# Discovery_Board.net
KiCad netlist of a schematic drawn in Altium Designer
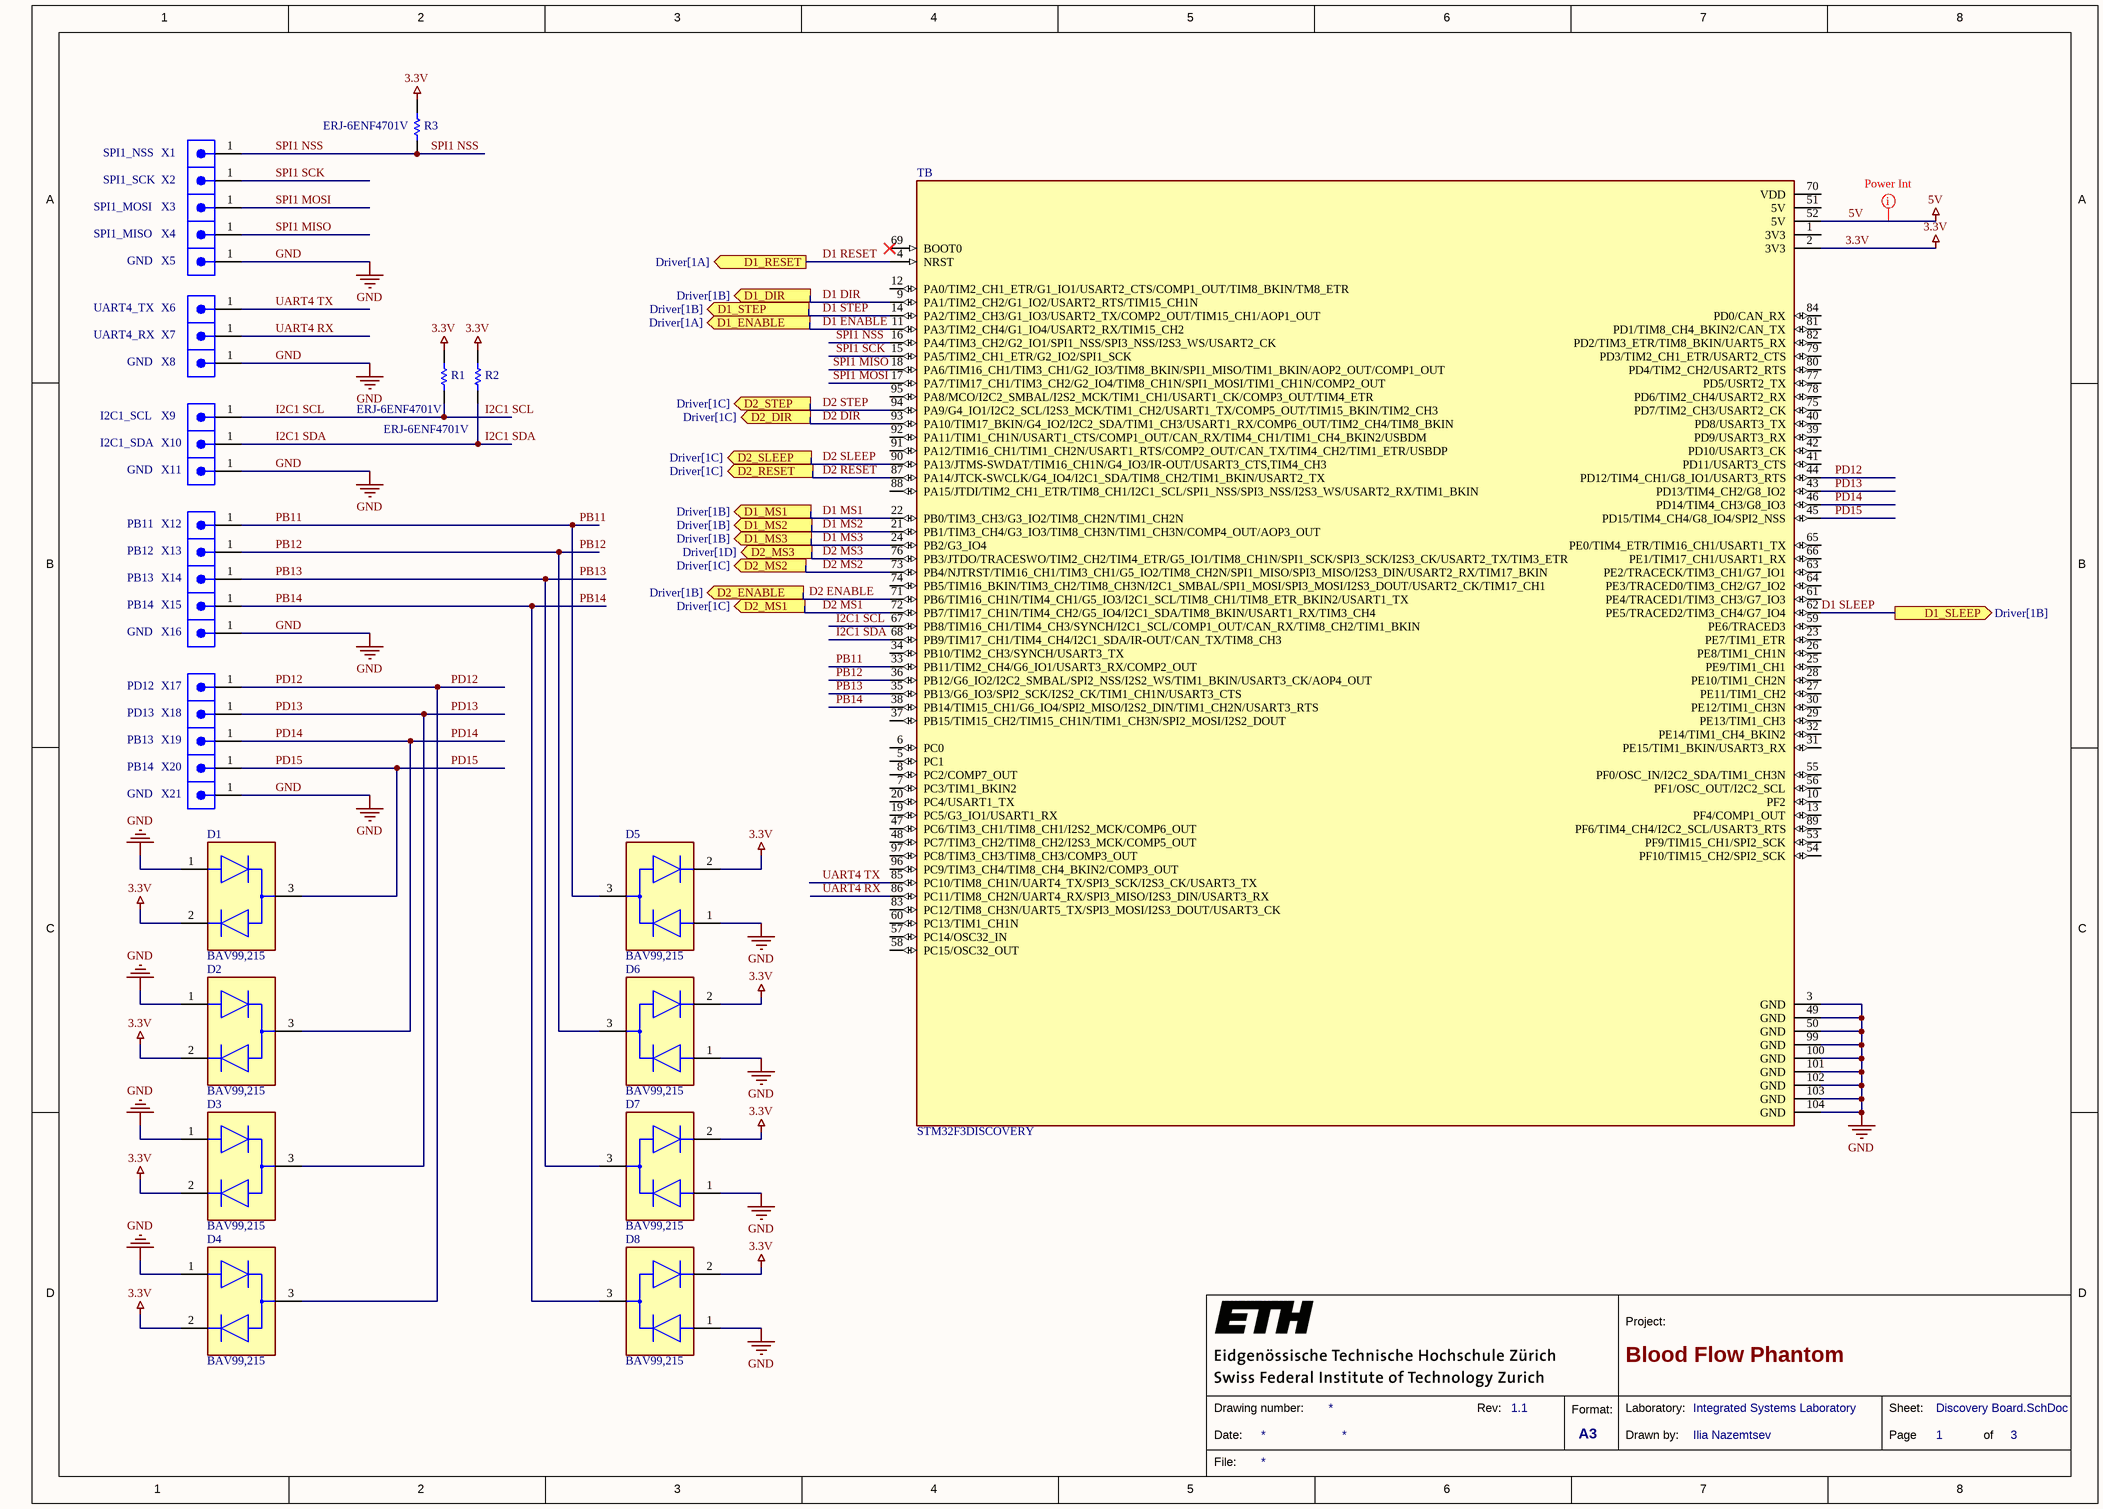
[diagram p0: Discovery Board.SchDoc]

(export (version "E")
  (design (tool "Eeschema 10.0.6"))
  (components
    (comp (ref "D1")
      (value "BAV99,215")
      (footprint "FP-SOT23-MFG")
      (description "DIODE ARRAY GP 100V 215MA SOT23")
      (libsource (lib "") (part "86a7eb6839269cc1691df5cbdd99f75_1"))
    )
    (comp (ref "D2")
      (value "BAV99,215")
      (footprint "FP-SOT23-MFG")
      (description "DIODE ARRAY GP 100V 215MA SOT23")
      (libsource (lib "") (part "86a7eb6839269cc1691df5cbdd99f75_1"))
    )
    (comp (ref "D3")
      (value "BAV99,215")
      (footprint "FP-SOT23-MFG")
      (description "DIODE ARRAY GP 100V 215MA SOT23")
      (libsource (lib "") (part "86a7eb6839269cc1691df5cbdd99f75_1"))
    )
    (comp (ref "D4")
      (value "BAV99,215")
      (footprint "FP-SOT23-MFG")
      (description "DIODE ARRAY GP 100V 215MA SOT23")
      (libsource (lib "") (part "86a7eb6839269cc1691df5cbdd99f75_1"))
    )
    (comp (ref "D5")
      (value "BAV99,215")
      (footprint "FP-SOT23-MFG")
      (description "DIODE ARRAY GP 100V 215MA SOT23")
      (libsource (lib "Altium Content Vault") (part "86a7eb6839269cc1691df5cbdd99f75"))
    )
    (comp (ref "D6")
      (value "BAV99,215")
      (footprint "FP-SOT23-MFG")
      (description "DIODE ARRAY GP 100V 215MA SOT23")
      (libsource (lib "Altium Content Vault") (part "86a7eb6839269cc1691df5cbdd99f75"))
    )
    (comp (ref "D7")
      (value "BAV99,215")
      (footprint "FP-SOT23-MFG")
      (description "DIODE ARRAY GP 100V 215MA SOT23")
      (libsource (lib "Altium Content Vault") (part "86a7eb6839269cc1691df5cbdd99f75"))
    )
    (comp (ref "D8")
      (value "BAV99,215")
      (footprint "FP-SOT23-MFG")
      (description "DIODE ARRAY GP 100V 215MA SOT23")
      (libsource (lib "Altium Content Vault") (part "86a7eb6839269cc1691df5cbdd99f75"))
    )
    (comp (ref "R1")
      (value "ERJ-6ENF4701V")
      (footprint "RESC2013X70X40NL20T20")
      (description "Chip Resistor, 4.7 KOhm, +/- 1%, 0.125 W, -55 to 155 degC, 0805 (2012 Metric), RoHS, Tape and Reel")
      (fields (field (name "MANUFACTURER") "Panasonic"))
      (libsource (lib "Altium Content Vault") (part "RES-2"))
    )
    (comp (ref "R2")
      (value "ERJ-6ENF4701V")
      (footprint "RESC2013X70X40NL20T20")
      (description "Chip Resistor, 4.7 KOhm, +/- 1%, 0.125 W, -55 to 155 degC, 0805 (2012 Metric), RoHS, Tape and Reel")
      (fields (field (name "MANUFACTURER") "Panasonic"))
      (libsource (lib "Altium Content Vault") (part "RES-2"))
    )
    (comp (ref "R3")
      (value "ERJ-6ENF4701V")
      (footprint "RESC2013X70X40NL20T20")
      (description "Chip Resistor, 4.7 KOhm, +/- 1%, 0.125 W, -55 to 155 degC, 0805 (2012 Metric), RoHS, Tape and Reel")
      (fields (field (name "MANUFACTURER") "Panasonic"))
      (libsource (lib "Altium Content Vault") (part "RES-2"))
    )
    (comp (ref "TB")
      (value "STM32F3DISCOVERY")
      (footprint "SHIELD_STM32F3DISCOVERY")
      (description "STM32F303VCT6 Discovery STM32F3 ARMÂ® CortexÂ®-M4 MCU 32-Bit Embedded Evaluation Board")
      (fields (field (name "MF") "STMicroelectronics"))
      (libsource (lib "SnapEDAsch") (part "STM32F3DISCOVERY"))
    )
    (comp (ref "X1")
      (value "SPI1_NSS")
      (footprint "68000-101HLF")
      (description "1 Positions Header, Unshrouded Connector  Through Hole Gold or Gold, GXT™")
      (fields
        (field (name "MANUFACTURER") "Amphenol FCI")
        (field (name "MANUFACTURER PART NUMBER") "68000-101HLF")
      )
      (libsource (lib "ETHZ Vault") (part "CON-1x1-Male"))
    )
    (comp (ref "X2")
      (value "SPI1_SCK")
      (footprint "68000-101HLF")
      (description "1 Positions Header, Unshrouded Connector  Through Hole Gold or Gold, GXT™")
      (fields
        (field (name "MANUFACTURER") "Amphenol FCI")
        (field (name "MANUFACTURER PART NUMBER") "68000-101HLF")
      )
      (libsource (lib "ETHZ Vault") (part "CON-1x1-Male"))
    )
    (comp (ref "X3")
      (value "SPI1_MOSI")
      (footprint "68000-101HLF")
      (description "1 Positions Header, Unshrouded Connector  Through Hole Gold or Gold, GXT™")
      (fields
        (field (name "MANUFACTURER") "Amphenol FCI")
        (field (name "MANUFACTURER PART NUMBER") "68000-101HLF")
      )
      (libsource (lib "ETHZ Vault") (part "CON-1x1-Male"))
    )
    (comp (ref "X4")
      (value "SPI1_MISO")
      (footprint "68000-101HLF")
      (description "1 Positions Header, Unshrouded Connector  Through Hole Gold or Gold, GXT™")
      (fields
        (field (name "MANUFACTURER") "Amphenol FCI")
        (field (name "MANUFACTURER PART NUMBER") "68000-101HLF")
      )
      (libsource (lib "ETHZ Vault") (part "CON-1x1-Male"))
    )
    (comp (ref "X5")
      (value "GND")
      (footprint "68000-101HLF")
      (description "1 Positions Header, Unshrouded Connector  Through Hole Gold or Gold, GXT™")
      (fields
        (field (name "MANUFACTURER") "Amphenol FCI")
        (field (name "MANUFACTURER PART NUMBER") "68000-101HLF")
      )
      (libsource (lib "ETHZ Vault") (part "CON-1x1-Male"))
    )
    (comp (ref "X6")
      (value "UART4_TX")
      (footprint "68000-101HLF")
      (description "1 Positions Header, Unshrouded Connector  Through Hole Gold or Gold, GXT™")
      (fields
        (field (name "MANUFACTURER") "Amphenol FCI")
        (field (name "MANUFACTURER PART NUMBER") "68000-101HLF")
      )
      (libsource (lib "ETHZ Vault") (part "CON-1x1-Male"))
    )
    (comp (ref "X7")
      (value "UART4_RX")
      (footprint "68000-101HLF")
      (description "1 Positions Header, Unshrouded Connector  Through Hole Gold or Gold, GXT™")
      (fields
        (field (name "MANUFACTURER") "Amphenol FCI")
        (field (name "MANUFACTURER PART NUMBER") "68000-101HLF")
      )
      (libsource (lib "ETHZ Vault") (part "CON-1x1-Male"))
    )
    (comp (ref "X8")
      (value "GND")
      (footprint "68000-101HLF")
      (description "1 Positions Header, Unshrouded Connector  Through Hole Gold or Gold, GXT™")
      (fields
        (field (name "MANUFACTURER") "Amphenol FCI")
        (field (name "MANUFACTURER PART NUMBER") "68000-101HLF")
      )
      (libsource (lib "ETHZ Vault") (part "CON-1x1-Male"))
    )
    (comp (ref "X9")
      (value "I2C1_SCL")
      (footprint "68000-101HLF")
      (description "1 Positions Header, Unshrouded Connector  Through Hole Gold or Gold, GXT™")
      (fields
        (field (name "MANUFACTURER") "Amphenol FCI")
        (field (name "MANUFACTURER PART NUMBER") "68000-101HLF")
      )
      (libsource (lib "ETHZ Vault") (part "CON-1x1-Male"))
    )
    (comp (ref "X10")
      (value "I2C1_SDA")
      (footprint "68000-101HLF")
      (description "1 Positions Header, Unshrouded Connector  Through Hole Gold or Gold, GXT™")
      (fields
        (field (name "MANUFACTURER") "Amphenol FCI")
        (field (name "MANUFACTURER PART NUMBER") "68000-101HLF")
      )
      (libsource (lib "ETHZ Vault") (part "CON-1x1-Male"))
    )
    (comp (ref "X11")
      (value "GND")
      (footprint "68000-101HLF")
      (description "1 Positions Header, Unshrouded Connector  Through Hole Gold or Gold, GXT™")
      (fields
        (field (name "MANUFACTURER") "Amphenol FCI")
        (field (name "MANUFACTURER PART NUMBER") "68000-101HLF")
      )
      (libsource (lib "ETHZ Vault") (part "CON-1x1-Male"))
    )
    (comp (ref "X12")
      (value "PB11")
      (footprint "68000-101HLF")
      (description "1 Positions Header, Unshrouded Connector  Through Hole Gold or Gold, GXT™")
      (fields
        (field (name "MANUFACTURER") "Amphenol FCI")
        (field (name "MANUFACTURER PART NUMBER") "68000-101HLF")
      )
      (libsource (lib "ETHZ Vault") (part "CON-1x1-Male"))
    )
    (comp (ref "X13")
      (value "PB12")
      (footprint "68000-101HLF")
      (description "1 Positions Header, Unshrouded Connector  Through Hole Gold or Gold, GXT™")
      (fields
        (field (name "MANUFACTURER") "Amphenol FCI")
        (field (name "MANUFACTURER PART NUMBER") "68000-101HLF")
      )
      (libsource (lib "ETHZ Vault") (part "CON-1x1-Male"))
    )
    (comp (ref "X14")
      (value "PB13")
      (footprint "68000-101HLF")
      (description "1 Positions Header, Unshrouded Connector  Through Hole Gold or Gold, GXT™")
      (fields
        (field (name "MANUFACTURER") "Amphenol FCI")
        (field (name "MANUFACTURER PART NUMBER") "68000-101HLF")
      )
      (libsource (lib "ETHZ Vault") (part "CON-1x1-Male"))
    )
    (comp (ref "X15")
      (value "PB14")
      (footprint "68000-101HLF")
      (description "1 Positions Header, Unshrouded Connector  Through Hole Gold or Gold, GXT™")
      (fields
        (field (name "MANUFACTURER") "Amphenol FCI")
        (field (name "MANUFACTURER PART NUMBER") "68000-101HLF")
      )
      (libsource (lib "ETHZ Vault") (part "CON-1x1-Male"))
    )
    (comp (ref "X16")
      (value "GND")
      (footprint "68000-101HLF")
      (description "1 Positions Header, Unshrouded Connector  Through Hole Gold or Gold, GXT™")
      (fields
        (field (name "MANUFACTURER") "Amphenol FCI")
        (field (name "MANUFACTURER PART NUMBER") "68000-101HLF")
      )
      (libsource (lib "ETHZ Vault") (part "CON-1x1-Male"))
    )
    (comp (ref "X17")
      (value "PD12")
      (footprint "68000-101HLF")
      (description "1 Positions Header, Unshrouded Connector  Through Hole Gold or Gold, GXT™")
      (fields
        (field (name "MANUFACTURER") "Amphenol FCI")
        (field (name "MANUFACTURER PART NUMBER") "68000-101HLF")
      )
      (libsource (lib "ETHZ Vault") (part "CON-1x1-Male"))
    )
    (comp (ref "X18")
      (value "PD13")
      (footprint "68000-101HLF")
      (description "1 Positions Header, Unshrouded Connector  Through Hole Gold or Gold, GXT™")
      (fields
        (field (name "MANUFACTURER") "Amphenol FCI")
        (field (name "MANUFACTURER PART NUMBER") "68000-101HLF")
      )
      (libsource (lib "ETHZ Vault") (part "CON-1x1-Male"))
    )
    (comp (ref "X19")
      (value "PB13")
      (footprint "68000-101HLF")
      (description "1 Positions Header, Unshrouded Connector  Through Hole Gold or Gold, GXT™")
      (fields
        (field (name "MANUFACTURER") "Amphenol FCI")
        (field (name "MANUFACTURER PART NUMBER") "68000-101HLF")
      )
      (libsource (lib "ETHZ Vault") (part "CON-1x1-Male"))
    )
    (comp (ref "X20")
      (value "PB14")
      (footprint "68000-101HLF")
      (description "1 Positions Header, Unshrouded Connector  Through Hole Gold or Gold, GXT™")
      (fields
        (field (name "MANUFACTURER") "Amphenol FCI")
        (field (name "MANUFACTURER PART NUMBER") "68000-101HLF")
      )
      (libsource (lib "ETHZ Vault") (part "CON-1x1-Male"))
    )
    (comp (ref "X21")
      (value "GND")
      (footprint "68000-101HLF")
      (description "1 Positions Header, Unshrouded Connector  Through Hole Gold or Gold, GXT™")
      (fields
        (field (name "MANUFACTURER") "Amphenol FCI")
        (field (name "MANUFACTURER PART NUMBER") "68000-101HLF")
      )
      (libsource (lib "ETHZ Vault") (part "CON-1x1-Male"))
    )
  )
  (nets
    (net (code "1") (name "/D1 DIR") (class "Default")
      (node (ref "TB") (pin "9") (pinfunction "PA1/TIM2_CH2/G1_IO2/USART2_RTS/TIM15_CH1N_9") (pintype "bidirectional"))
    )
    (net (code "2") (name "/D1 ENABLE") (class "Default")
      (node (ref "TB") (pin "11") (pinfunction "PA3/TIM2_CH4/G1_IO4/USART2_RX/TIM15_CH2_11") (pintype "bidirectional"))
    )
    (net (code "3") (name "/D1 MS1") (class "Default")
      (node (ref "TB") (pin "22") (pinfunction "PB0/TIM3_CH3/G3_IO2/TIM8_CH2N/TIM1_CH2N_22") (pintype "bidirectional"))
    )
    (net (code "4") (name "/D1 MS2") (class "Default")
      (node (ref "TB") (pin "21") (pinfunction "PB1/TIM3_CH4/G3_IO3/TIM8_CH3N/TIM1_CH3N/COMP4_OUT/AOP3_OUT_21") (pintype "bidirectional"))
    )
    (net (code "5") (name "/D1 MS3") (class "Default")
      (node (ref "TB") (pin "24") (pinfunction "PB2/G3_IO4_24") (pintype "bidirectional"))
    )
    (net (code "6") (name "/D1 RESET") (class "Default")
      (node (ref "TB") (pin "4") (pinfunction "NRST_4") (pintype "input"))
    )
    (net (code "7") (name "/D1 SLEEP") (class "Default")
      (node (ref "TB") (pin "62") (pinfunction "PE5/TRACED2/TIM3_CH4/G7_IO4_62") (pintype "bidirectional"))
    )
    (net (code "8") (name "/D1 STEP") (class "Default")
      (node (ref "TB") (pin "14") (pinfunction "PA2/TIM2_CH3/G1_IO3/USART2_TX/COMP2_OUT/TIM15_CH1/AOP1_OUT_14") (pintype "bidirectional"))
    )
    (net (code "9") (name "/D2 DIR") (class "Default")
      (node (ref "TB") (pin "93") (pinfunction "PA10/TIM17_BKIN/G4_IO2/I2C2_SDA/TIM1_CH3/USART1_RX/COMP6_OUT/TIM2_CH4/TIM8_BKIN_93") (pintype "bidirectional"))
    )
    (net (code "10") (name "/D2 ENABLE") (class "Default")
      (node (ref "TB") (pin "71") (pinfunction "PB6/TIM16_CH1N/TIM4_CH1/G5_IO3/I2C1_SCL/TIM8_CH1/TIM8_ETR_BKIN2/USART1_TX_71") (pintype "bidirectional"))
    )
    (net (code "11") (name "/D2 MS1") (class "Default")
      (node (ref "TB") (pin "72") (pinfunction "PB7/TIM17_CH1N/TIM4_CH2/G5_IO4/I2C1_SDA/TIM8_BKIN/USART1_RX/TIM3_CH4_72") (pintype "bidirectional"))
    )
    (net (code "12") (name "/D2 MS2") (class "Default")
      (node (ref "TB") (pin "73") (pinfunction "PB4/NJTRST/TIM16_CH1/TIM3_CH1/G5_IO2/TIM8_CH2N/SPI1_MISO/SPI3_MISO/I2S3_DIN/USART2_RX/TIM17_BKIN_73") (pintype "bidirectional"))
    )
    (net (code "13") (name "/D2 MS3") (class "Default")
      (node (ref "TB") (pin "76") (pinfunction "PB3/JTDO/TRACESWO/TIM2_CH2/TIM4_ETR/G5_IO1/TIM8_CH1N/SPI1_SCK/SPI3_SCK/I2S3_CK/USART2_TX/TIM3_ETR_76") (pintype "bidirectional"))
    )
    (net (code "14") (name "/D2 RESET") (class "Default")
      (node (ref "TB") (pin "87") (pinfunction "PA14/JTCK-SWCLK/G4_IO4/I2C1_SDA/TIM8_CH2/TIM1_BKIN/USART2_TX_87") (pintype "bidirectional"))
    )
    (net (code "15") (name "/D2 SLEEP") (class "Default")
      (node (ref "TB") (pin "90") (pinfunction "PA13/JTMS-SWDAT/TIM16_CH1N/G4_IO3/IR-OUT/USART3_CTS,TIM4_CH3_90") (pintype "bidirectional"))
    )
    (net (code "16") (name "/D2 STEP") (class "Default")
      (node (ref "TB") (pin "94") (pinfunction "PA9/G4_IO1/I2C2_SCL/I2S3_MCK/TIM1_CH2/USART1_TX/COMP5_OUT/TIM15_BKIN/TIM2_CH3_94") (pintype "bidirectional"))
    )
    (net (code "17") (name "/I2C1 SCL") (class "Default")
      (node (ref "R1") (pin "2") (pinfunction "2_2") (pintype "passive"))
      (node (ref "TB") (pin "67") (pinfunction "PB8/TIM16_CH1/TIM4_CH3/SYNCH/I2C1_SCL/COMP1_OUT/CAN_RX/TIM8_CH2/TIM1_BKIN_67") (pintype "bidirectional"))
      (node (ref "X9") (pin "1") (pinfunction "1_1") (pintype "passive"))
    )
    (net (code "18") (name "/I2C1 SDA") (class "Default")
      (node (ref "R2") (pin "2") (pinfunction "2_2") (pintype "passive"))
      (node (ref "TB") (pin "68") (pinfunction "PB9/TIM17_CH1/TIM4_CH4/I2C1_SDA/IR-OUT/CAN_TX/TIM8_CH3_68") (pintype "bidirectional"))
      (node (ref "X10") (pin "1") (pinfunction "1_1") (pintype "passive"))
    )
    (net (code "19") (name "/PB11") (class "Default")
      (node (ref "D5") (pin "3") (pinfunction "3_3") (pintype "passive"))
      (node (ref "TB") (pin "33") (pinfunction "PB11/TIM2_CH4/G6_IO1/USART3_RX/COMP2_OUT_33") (pintype "bidirectional"))
      (node (ref "X12") (pin "1") (pinfunction "1_1") (pintype "passive"))
    )
    (net (code "20") (name "/PB12") (class "Default")
      (node (ref "D6") (pin "3") (pinfunction "3_3") (pintype "passive"))
      (node (ref "TB") (pin "36") (pinfunction "PB12/G6_IO2/I2C2_SMBAL/SPI2_NSS/I2S2_WS/TIM1_BKIN/USART3_CK/AOP4_OUT_36") (pintype "bidirectional"))
      (node (ref "X13") (pin "1") (pinfunction "1_1") (pintype "passive"))
    )
    (net (code "21") (name "/PB13") (class "Default")
      (node (ref "D7") (pin "3") (pinfunction "3_3") (pintype "passive"))
      (node (ref "TB") (pin "35") (pinfunction "PB13/G6_IO3/SPI2_SCK/I2S2_CK/TIM1_CH1N/USART3_CTS_35") (pintype "bidirectional"))
      (node (ref "X14") (pin "1") (pinfunction "1_1") (pintype "passive"))
    )
    (net (code "22") (name "/PB14") (class "Default")
      (node (ref "D8") (pin "3") (pinfunction "3_3") (pintype "passive"))
      (node (ref "TB") (pin "38") (pinfunction "PB14/TIM15_CH1/G6_IO4/SPI2_MISO/I2S2_DIN/TIM1_CH2N/USART3_RTS_38") (pintype "bidirectional"))
      (node (ref "X15") (pin "1") (pinfunction "1_1") (pintype "passive"))
    )
    (net (code "23") (name "/PD12") (class "Default")
      (node (ref "D4") (pin "3") (pinfunction "3_3") (pintype "passive"))
      (node (ref "TB") (pin "44") (pinfunction "PD12/TIM4_CH1/G8_IO1/USART3_RTS_44") (pintype "bidirectional"))
      (node (ref "X17") (pin "1") (pinfunction "1_1") (pintype "passive"))
    )
    (net (code "24") (name "/PD13") (class "Default")
      (node (ref "D3") (pin "3") (pinfunction "3_3") (pintype "passive"))
      (node (ref "TB") (pin "43") (pinfunction "PD13/TIM4_CH2/G8_IO2_43") (pintype "bidirectional"))
      (node (ref "X18") (pin "1") (pinfunction "1_1") (pintype "passive"))
    )
    (net (code "25") (name "/PD14") (class "Default")
      (node (ref "D2") (pin "3") (pinfunction "3_3") (pintype "passive"))
      (node (ref "TB") (pin "46") (pinfunction "PD14/TIM4_CH3/G8_IO3_46") (pintype "bidirectional"))
      (node (ref "X19") (pin "1") (pinfunction "1_1") (pintype "passive"))
    )
    (net (code "26") (name "/PD15") (class "Default")
      (node (ref "D1") (pin "3") (pinfunction "3_3") (pintype "passive"))
      (node (ref "TB") (pin "45") (pinfunction "PD15/TIM4_CH4/G8_IO4/SPI2_NSS_45") (pintype "bidirectional"))
      (node (ref "X20") (pin "1") (pinfunction "1_1") (pintype "passive"))
    )
    (net (code "27") (name "/SPI1 MISO") (class "Default")
      (node (ref "TB") (pin "18") (pinfunction "PA6/TIM16_CH1/TIM3_CH1/G2_IO3/TIM8_BKIN/SPI1_MISO/TIM1_BKIN/AOP2_OUT/COMP1_OUT_18") (pintype "bidirectional"))
      (node (ref "X4") (pin "1") (pinfunction "1_1") (pintype "passive"))
    )
    (net (code "28") (name "/SPI1 MOSI") (class "Default")
      (node (ref "TB") (pin "17") (pinfunction "PA7/TIM17_CH1/TIM3_CH2/G2_IO4/TIM8_CH1N/SPI1_MOSI/TIM1_CH1N/COMP2_OUT_17") (pintype "bidirectional"))
      (node (ref "X3") (pin "1") (pinfunction "1_1") (pintype "passive"))
    )
    (net (code "29") (name "/SPI1 NSS") (class "Default")
      (node (ref "R3") (pin "2") (pinfunction "2_2") (pintype "passive"))
      (node (ref "TB") (pin "16") (pinfunction "PA4/TIM3_CH2/G2_IO1/SPI1_NSS/SPI3_NSS/I2S3_WS/USART2_CK_16") (pintype "bidirectional"))
      (node (ref "X1") (pin "1") (pinfunction "1_1") (pintype "passive"))
    )
    (net (code "30") (name "/SPI1 SCK") (class "Default")
      (node (ref "TB") (pin "15") (pinfunction "PA5/TIM2_CH1_ETR/G2_IO2/SPI1_SCK_15") (pintype "bidirectional"))
      (node (ref "X2") (pin "1") (pinfunction "1_1") (pintype "passive"))
    )
    (net (code "31") (name "/UART4 RX") (class "Default")
      (node (ref "TB") (pin "86") (pinfunction "PC11/TIM8_CH2N/UART4_RX/SPI3_MISO/I2S3_DIN/USART3_RX_86") (pintype "bidirectional"))
      (node (ref "X7") (pin "1") (pinfunction "1_1") (pintype "passive"))
    )
    (net (code "32") (name "/UART4 TX") (class "Default")
      (node (ref "TB") (pin "85") (pinfunction "PC10/TIM8_CH1N/UART4_TX/SPI3_SCK/I2S3_CK/USART3_TX_85") (pintype "bidirectional"))
      (node (ref "X6") (pin "1") (pinfunction "1_1") (pintype "passive"))
    )
    (net (code "33") (name "3.3V") (class "Default")
      (node (ref "D1") (pin "2") (pinfunction "2_2") (pintype "passive"))
      (node (ref "D2") (pin "2") (pinfunction "2_2") (pintype "passive"))
      (node (ref "D3") (pin "2") (pinfunction "2_2") (pintype "passive"))
      (node (ref "D4") (pin "2") (pinfunction "2_2") (pintype "passive"))
      (node (ref "D5") (pin "2") (pinfunction "2_2") (pintype "passive"))
      (node (ref "D6") (pin "2") (pinfunction "2_2") (pintype "passive"))
      (node (ref "D7") (pin "2") (pinfunction "2_2") (pintype "passive"))
      (node (ref "D8") (pin "2") (pinfunction "2_2") (pintype "passive"))
      (node (ref "R1") (pin "1") (pinfunction "1_1") (pintype "passive"))
      (node (ref "R2") (pin "1") (pinfunction "1_1") (pintype "passive"))
      (node (ref "R3") (pin "1") (pinfunction "1_1") (pintype "passive"))
      (node (ref "TB") (pin "2") (pinfunction "3V3_2") (pintype "power_in"))
    )
    (net (code "34") (name "5V") (class "Default")
      (node (ref "TB") (pin "52") (pinfunction "5V_52") (pintype "power_in"))
    )
    (net (code "35") (name "GND") (class "Default")
      (node (ref "D1") (pin "1") (pinfunction "1_1") (pintype "passive"))
      (node (ref "D2") (pin "1") (pinfunction "1_1") (pintype "passive"))
      (node (ref "D3") (pin "1") (pinfunction "1_1") (pintype "passive"))
      (node (ref "D4") (pin "1") (pinfunction "1_1") (pintype "passive"))
      (node (ref "D5") (pin "1") (pinfunction "1_1") (pintype "passive"))
      (node (ref "D6") (pin "1") (pinfunction "1_1") (pintype "passive"))
      (node (ref "D7") (pin "1") (pinfunction "1_1") (pintype "passive"))
      (node (ref "D8") (pin "1") (pinfunction "1_1") (pintype "passive"))
      (node (ref "TB") (pin "100") (pinfunction "GND_100") (pintype "power_in"))
      (node (ref "TB") (pin "101") (pinfunction "GND_101") (pintype "power_in"))
      (node (ref "TB") (pin "102") (pinfunction "GND_102") (pintype "power_in"))
      (node (ref "TB") (pin "103") (pinfunction "GND_103") (pintype "power_in"))
      (node (ref "TB") (pin "104") (pinfunction "GND_104") (pintype "power_in"))
      (node (ref "TB") (pin "3") (pinfunction "GND_3") (pintype "power_in"))
      (node (ref "TB") (pin "49") (pinfunction "GND_49") (pintype "power_in"))
      (node (ref "TB") (pin "50") (pinfunction "GND_50") (pintype "power_in"))
      (node (ref "TB") (pin "99") (pinfunction "GND_99") (pintype "power_in"))
      (node (ref "X11") (pin "1") (pinfunction "1_1") (pintype "passive"))
      (node (ref "X16") (pin "1") (pinfunction "1_1") (pintype "passive"))
      (node (ref "X21") (pin "1") (pinfunction "1_1") (pintype "passive"))
      (node (ref "X5") (pin "1") (pinfunction "1_1") (pintype "passive"))
      (node (ref "X8") (pin "1") (pinfunction "1_1") (pintype "passive"))
    )
    (net (code "36") (name "unconnected-(TB-3V3-Pad1)") (class "Default")
      (node (ref "TB") (pin "1") (pinfunction "3V3_1") (pintype "power_in"))
    )
    (net (code "37") (name "unconnected-(TB-5V-Pad51)") (class "Default")
      (node (ref "TB") (pin "51") (pinfunction "5V_51") (pintype "power_in"))
    )
    (net (code "38") (name "unconnected-(TB-BOOT0-Pad69)") (class "Default")
      (node (ref "TB") (pin "69") (pinfunction "BOOT0_69") (pintype "input+no_connect"))
    )
    (net (code "39") (name "unconnected-(TB-PA0{slash}TIM2_CH1_ETR{slash}G1_IO1{slash}USART2_CTS{slash}COMP1_OUT{slash}TIM8_BKIN{slash}TM8_ETR-Pad12)") (class "Default")
      (node (ref "TB") (pin "12") (pinfunction "PA0/TIM2_CH1_ETR/G1_IO1/USART2_CTS/COMP1_OUT/TIM8_BKIN/TM8_ETR_12") (pintype "bidirectional"))
    )
    (net (code "40") (name "unconnected-(TB-PA8{slash}MCO{slash}I2C2_SMBAL{slash}I2S2_MCK{slash}TIM1_CH1{slash}USART1_CK{slash}COMP3_OUT{slash}TIM4_ETR-Pad95)") (class "Default")
      (node (ref "TB") (pin "95") (pinfunction "PA8/MCO/I2C2_SMBAL/I2S2_MCK/TIM1_CH1/USART1_CK/COMP3_OUT/TIM4_ETR_95") (pintype "bidirectional"))
    )
    (net (code "41") (name "unconnected-(TB-PA11{slash}TIM1_CH1N{slash}USART1_CTS{slash}COMP1_OUT{slash}CAN_RX{slash}TIM4_CH1{slash}TIM1_CH4_BKIN2{slash}USBDM-Pad92)") (class "Default")
      (node (ref "TB") (pin "92") (pinfunction "PA11/TIM1_CH1N/USART1_CTS/COMP1_OUT/CAN_RX/TIM4_CH1/TIM1_CH4_BKIN2/USBDM_92") (pintype "bidirectional"))
    )
    (net (code "42") (name "unconnected-(TB-PA12{slash}TIM16_CH1{slash}TIM1_CH2N{slash}USART1_RTS{slash}COMP2_OUT{slash}CAN_TX{slash}TIM4_CH2{slash}TIM1_ETR{slash}USBDP-Pad91)") (class "Default")
      (node (ref "TB") (pin "91") (pinfunction "PA12/TIM16_CH1/TIM1_CH2N/USART1_RTS/COMP2_OUT/CAN_TX/TIM4_CH2/TIM1_ETR/USBDP_91") (pintype "bidirectional"))
    )
    (net (code "43") (name "unconnected-(TB-PA15{slash}JTDI{slash}TIM2_CH1_ETR{slash}TIM8_CH1{slash}I2C1_SCL{slash}SPI1_NSS{slash}SPI3_NSS{slash}I2S3_WS{slash}USART2_RX{slash}TIM1_BKIN-Pad88)") (class "Default")
      (node (ref "TB") (pin "88") (pinfunction "PA15/JTDI/TIM2_CH1_ETR/TIM8_CH1/I2C1_SCL/SPI1_NSS/SPI3_NSS/I2S3_WS/USART2_RX/TIM1_BKIN_88") (pintype "bidirectional"))
    )
    (net (code "44") (name "unconnected-(TB-PB5{slash}TIM16_BKIN{slash}TIM3_CH2{slash}TIM8_CH3N{slash}I2C1_SMBAL{slash}SPI1_MOSI{slash}SPI3_MOSI{slash}I2S3_DOUT{slash}USART2_CK{slash}TIM17_CH1-Pad74)") (class "Default")
      (node (ref "TB") (pin "74") (pinfunction "PB5/TIM16_BKIN/TIM3_CH2/TIM8_CH3N/I2C1_SMBAL/SPI1_MOSI/SPI3_MOSI/I2S3_DOUT/USART2_CK/TIM17_CH1_74") (pintype "bidirectional"))
    )
    (net (code "45") (name "unconnected-(TB-PB10{slash}TIM2_CH3{slash}SYNCH{slash}USART3_TX-Pad34)") (class "Default")
      (node (ref "TB") (pin "34") (pinfunction "PB10/TIM2_CH3/SYNCH/USART3_TX_34") (pintype "bidirectional"))
    )
    (net (code "46") (name "unconnected-(TB-PB15{slash}TIM15_CH2{slash}TIM15_CH1N{slash}TIM1_CH3N{slash}SPI2_MOSI{slash}I2S2_DOUT-Pad37)") (class "Default")
      (node (ref "TB") (pin "37") (pinfunction "PB15/TIM15_CH2/TIM15_CH1N/TIM1_CH3N/SPI2_MOSI/I2S2_DOUT_37") (pintype "bidirectional"))
    )
    (net (code "47") (name "unconnected-(TB-PC0-Pad6)") (class "Default")
      (node (ref "TB") (pin "6") (pinfunction "PC0_6") (pintype "bidirectional"))
    )
    (net (code "48") (name "unconnected-(TB-PC1-Pad5)") (class "Default")
      (node (ref "TB") (pin "5") (pinfunction "PC1_5") (pintype "bidirectional"))
    )
    (net (code "49") (name "unconnected-(TB-PC2{slash}COMP7_OUT-Pad8)") (class "Default")
      (node (ref "TB") (pin "8") (pinfunction "PC2/COMP7_OUT_8") (pintype "bidirectional"))
    )
    (net (code "50") (name "unconnected-(TB-PC3{slash}TIM1_BKIN2-Pad7)") (class "Default")
      (node (ref "TB") (pin "7") (pinfunction "PC3/TIM1_BKIN2_7") (pintype "bidirectional"))
    )
    (net (code "51") (name "unconnected-(TB-PC4{slash}USART1_TX-Pad20)") (class "Default")
      (node (ref "TB") (pin "20") (pinfunction "PC4/USART1_TX_20") (pintype "bidirectional"))
    )
    (net (code "52") (name "unconnected-(TB-PC5{slash}G3_IO1{slash}USART1_RX-Pad19)") (class "Default")
      (node (ref "TB") (pin "19") (pinfunction "PC5/G3_IO1/USART1_RX_19") (pintype "bidirectional"))
    )
    (net (code "53") (name "unconnected-(TB-PC6{slash}TIM3_CH1{slash}TIM8_CH1{slash}I2S2_MCK{slash}COMP6_OUT-Pad47)") (class "Default")
      (node (ref "TB") (pin "47") (pinfunction "PC6/TIM3_CH1/TIM8_CH1/I2S2_MCK/COMP6_OUT_47") (pintype "bidirectional"))
    )
    (net (code "54") (name "unconnected-(TB-PC7{slash}TIM3_CH2{slash}TIM8_CH2{slash}I2S3_MCK{slash}COMP5_OUT-Pad48)") (class "Default")
      (node (ref "TB") (pin "48") (pinfunction "PC7/TIM3_CH2/TIM8_CH2/I2S3_MCK/COMP5_OUT_48") (pintype "bidirectional"))
    )
    (net (code "55") (name "unconnected-(TB-PC8{slash}TIM3_CH3{slash}TIM8_CH3{slash}COMP3_OUT-Pad97)") (class "Default")
      (node (ref "TB") (pin "97") (pinfunction "PC8/TIM3_CH3/TIM8_CH3/COMP3_OUT_97") (pintype "bidirectional"))
    )
    (net (code "56") (name "unconnected-(TB-PC9{slash}TIM3_CH4{slash}TIM8_CH4_BKIN2{slash}COMP3_OUT-Pad96)") (class "Default")
      (node (ref "TB") (pin "96") (pinfunction "PC9/TIM3_CH4/TIM8_CH4_BKIN2/COMP3_OUT_96") (pintype "bidirectional"))
    )
    (net (code "57") (name "unconnected-(TB-PC12{slash}TIM8_CH3N{slash}UART5_TX{slash}SPI3_MOSI{slash}I2S3_DOUT{slash}USART3_CK-Pad83)") (class "Default")
      (node (ref "TB") (pin "83") (pinfunction "PC12/TIM8_CH3N/UART5_TX/SPI3_MOSI/I2S3_DOUT/USART3_CK_83") (pintype "bidirectional"))
    )
    (net (code "58") (name "unconnected-(TB-PC13{slash}TIM1_CH1N-Pad60)") (class "Default")
      (node (ref "TB") (pin "60") (pinfunction "PC13/TIM1_CH1N_60") (pintype "bidirectional"))
    )
    (net (code "59") (name "unconnected-(TB-PC14{slash}OSC32_IN-Pad57)") (class "Default")
      (node (ref "TB") (pin "57") (pinfunction "PC14/OSC32_IN_57") (pintype "bidirectional"))
    )
    (net (code "60") (name "unconnected-(TB-PC15{slash}OSC32_OUT-Pad58)") (class "Default")
      (node (ref "TB") (pin "58") (pinfunction "PC15/OSC32_OUT_58") (pintype "bidirectional"))
    )
    (net (code "61") (name "unconnected-(TB-PD0{slash}CAN_RX-Pad84)") (class "Default")
      (node (ref "TB") (pin "84") (pinfunction "PD0/CAN_RX_84") (pintype "bidirectional"))
    )
    (net (code "62") (name "unconnected-(TB-PD1{slash}TIM8_CH4_BKIN2{slash}CAN_TX-Pad81)") (class "Default")
      (node (ref "TB") (pin "81") (pinfunction "PD1/TIM8_CH4_BKIN2/CAN_TX_81") (pintype "bidirectional"))
    )
    (net (code "63") (name "unconnected-(TB-PD2{slash}TIM3_ETR{slash}TIM8_BKIN{slash}UART5_RX-Pad82)") (class "Default")
      (node (ref "TB") (pin "82") (pinfunction "PD2/TIM3_ETR/TIM8_BKIN/UART5_RX_82") (pintype "bidirectional"))
    )
    (net (code "64") (name "unconnected-(TB-PD3{slash}TIM2_CH1_ETR{slash}USART2_CTS-Pad79)") (class "Default")
      (node (ref "TB") (pin "79") (pinfunction "PD3/TIM2_CH1_ETR/USART2_CTS_79") (pintype "bidirectional"))
    )
    (net (code "65") (name "unconnected-(TB-PD4{slash}TIM2_CH2{slash}USART2_RTS-Pad80)") (class "Default")
      (node (ref "TB") (pin "80") (pinfunction "PD4/TIM2_CH2/USART2_RTS_80") (pintype "bidirectional"))
    )
    (net (code "66") (name "unconnected-(TB-PD5{slash}USRT2_TX-Pad77)") (class "Default")
      (node (ref "TB") (pin "77") (pinfunction "PD5/USRT2_TX_77") (pintype "bidirectional"))
    )
    (net (code "67") (name "unconnected-(TB-PD6{slash}TIM2_CH4{slash}USART2_RX-Pad78)") (class "Default")
      (node (ref "TB") (pin "78") (pinfunction "PD6/TIM2_CH4/USART2_RX_78") (pintype "bidirectional"))
    )
    (net (code "68") (name "unconnected-(TB-PD7{slash}TIM2_CH3{slash}USART2_CK-Pad75)") (class "Default")
      (node (ref "TB") (pin "75") (pinfunction "PD7/TIM2_CH3/USART2_CK_75") (pintype "bidirectional"))
    )
    (net (code "69") (name "unconnected-(TB-PD8{slash}USART3_TX-Pad40)") (class "Default")
      (node (ref "TB") (pin "40") (pinfunction "PD8/USART3_TX_40") (pintype "bidirectional"))
    )
    (net (code "70") (name "unconnected-(TB-PD9{slash}USART3_RX-Pad39)") (class "Default")
      (node (ref "TB") (pin "39") (pinfunction "PD9/USART3_RX_39") (pintype "bidirectional"))
    )
    (net (code "71") (name "unconnected-(TB-PD10{slash}USART3_CK-Pad42)") (class "Default")
      (node (ref "TB") (pin "42") (pinfunction "PD10/USART3_CK_42") (pintype "bidirectional"))
    )
    (net (code "72") (name "unconnected-(TB-PD11{slash}USART3_CTS-Pad41)") (class "Default")
      (node (ref "TB") (pin "41") (pinfunction "PD11/USART3_CTS_41") (pintype "bidirectional"))
    )
    (net (code "73") (name "unconnected-(TB-PE0{slash}TIM4_ETR{slash}TIM16_CH1{slash}USART1_TX-Pad65)") (class "Default")
      (node (ref "TB") (pin "65") (pinfunction "PE0/TIM4_ETR/TIM16_CH1/USART1_TX_65") (pintype "bidirectional"))
    )
    (net (code "74") (name "unconnected-(TB-PE1{slash}TIM17_CH1{slash}USART1_RX-Pad66)") (class "Default")
      (node (ref "TB") (pin "66") (pinfunction "PE1/TIM17_CH1/USART1_RX_66") (pintype "bidirectional"))
    )
    (net (code "75") (name "unconnected-(TB-PE2{slash}TRACECK{slash}TIM3_CH1{slash}G7_IO1-Pad63)") (class "Default")
      (node (ref "TB") (pin "63") (pinfunction "PE2/TRACECK/TIM3_CH1/G7_IO1_63") (pintype "bidirectional"))
    )
    (net (code "76") (name "unconnected-(TB-PE3{slash}TRACED0{slash}TIM3_CH2{slash}G7_IO2-Pad64)") (class "Default")
      (node (ref "TB") (pin "64") (pinfunction "PE3/TRACED0/TIM3_CH2/G7_IO2_64") (pintype "bidirectional"))
    )
    (net (code "77") (name "unconnected-(TB-PE4{slash}TRACED1{slash}TIM3_CH3{slash}G7_IO3-Pad61)") (class "Default")
      (node (ref "TB") (pin "61") (pinfunction "PE4/TRACED1/TIM3_CH3/G7_IO3_61") (pintype "bidirectional"))
    )
    (net (code "78") (name "unconnected-(TB-PE6{slash}TRACED3-Pad59)") (class "Default")
      (node (ref "TB") (pin "59") (pinfunction "PE6/TRACED3_59") (pintype "bidirectional"))
    )
    (net (code "79") (name "unconnected-(TB-PE7{slash}TIM1_ETR-Pad23)") (class "Default")
      (node (ref "TB") (pin "23") (pinfunction "PE7/TIM1_ETR_23") (pintype "bidirectional"))
    )
    (net (code "80") (name "unconnected-(TB-PE8{slash}TIM1_CH1N-Pad26)") (class "Default")
      (node (ref "TB") (pin "26") (pinfunction "PE8/TIM1_CH1N_26") (pintype "bidirectional"))
    )
    (net (code "81") (name "unconnected-(TB-PE9{slash}TIM1_CH1-Pad25)") (class "Default")
      (node (ref "TB") (pin "25") (pinfunction "PE9/TIM1_CH1_25") (pintype "bidirectional"))
    )
    (net (code "82") (name "unconnected-(TB-PE10{slash}TIM1_CH2N-Pad28)") (class "Default")
      (node (ref "TB") (pin "28") (pinfunction "PE10/TIM1_CH2N_28") (pintype "bidirectional"))
    )
    (net (code "83") (name "unconnected-(TB-PE11{slash}TIM1_CH2-Pad27)") (class "Default")
      (node (ref "TB") (pin "27") (pinfunction "PE11/TIM1_CH2_27") (pintype "bidirectional"))
    )
    (net (code "84") (name "unconnected-(TB-PE12{slash}TIM1_CH3N-Pad30)") (class "Default")
      (node (ref "TB") (pin "30") (pinfunction "PE12/TIM1_CH3N_30") (pintype "bidirectional"))
    )
    (net (code "85") (name "unconnected-(TB-PE13{slash}TIM1_CH3-Pad29)") (class "Default")
      (node (ref "TB") (pin "29") (pinfunction "PE13/TIM1_CH3_29") (pintype "bidirectional"))
    )
    (net (code "86") (name "unconnected-(TB-PE14{slash}TIM1_CH4_BKIN2-Pad32)") (class "Default")
      (node (ref "TB") (pin "32") (pinfunction "PE14/TIM1_CH4_BKIN2_32") (pintype "bidirectional"))
    )
    (net (code "87") (name "unconnected-(TB-PE15{slash}TIM1_BKIN{slash}USART3_RX-Pad31)") (class "Default")
      (node (ref "TB") (pin "31") (pinfunction "PE15/TIM1_BKIN/USART3_RX_31") (pintype "bidirectional"))
    )
    (net (code "88") (name "unconnected-(TB-PF0{slash}OSC_IN{slash}I2C2_SDA{slash}TIM1_CH3N-Pad55)") (class "Default")
      (node (ref "TB") (pin "55") (pinfunction "PF0/OSC_IN/I2C2_SDA/TIM1_CH3N_55") (pintype "bidirectional"))
    )
    (net (code "89") (name "unconnected-(TB-PF1{slash}OSC_OUT{slash}I2C2_SCL-Pad56)") (class "Default")
      (node (ref "TB") (pin "56") (pinfunction "PF1/OSC_OUT/I2C2_SCL_56") (pintype "bidirectional"))
    )
    (net (code "90") (name "unconnected-(TB-PF2-Pad10)") (class "Default")
      (node (ref "TB") (pin "10") (pinfunction "PF2_10") (pintype "bidirectional"))
    )
    (net (code "91") (name "unconnected-(TB-PF4{slash}COMP1_OUT-Pad13)") (class "Default")
      (node (ref "TB") (pin "13") (pinfunction "PF4/COMP1_OUT_13") (pintype "bidirectional"))
    )
    (net (code "92") (name "unconnected-(TB-PF6{slash}TIM4_CH4{slash}I2C2_SCL{slash}USART3_RTS-Pad89)") (class "Default")
      (node (ref "TB") (pin "89") (pinfunction "PF6/TIM4_CH4/I2C2_SCL/USART3_RTS_89") (pintype "bidirectional"))
    )
    (net (code "93") (name "unconnected-(TB-PF9{slash}TIM15_CH1{slash}SPI2_SCK-Pad53)") (class "Default")
      (node (ref "TB") (pin "53") (pinfunction "PF9/TIM15_CH1/SPI2_SCK_53") (pintype "bidirectional"))
    )
    (net (code "94") (name "unconnected-(TB-PF10{slash}TIM15_CH2{slash}SPI2_SCK-Pad54)") (class "Default")
      (node (ref "TB") (pin "54") (pinfunction "PF10/TIM15_CH2/SPI2_SCK_54") (pintype "bidirectional"))
    )
    (net (code "95") (name "unconnected-(TB-VDD-Pad70)") (class "Default")
      (node (ref "TB") (pin "70") (pinfunction "VDD_70") (pintype "power_in"))
    )
  )
)
